# ATX12V_MAIN_VERT.net
KiCad netlist of a schematic drawn in EAGLE
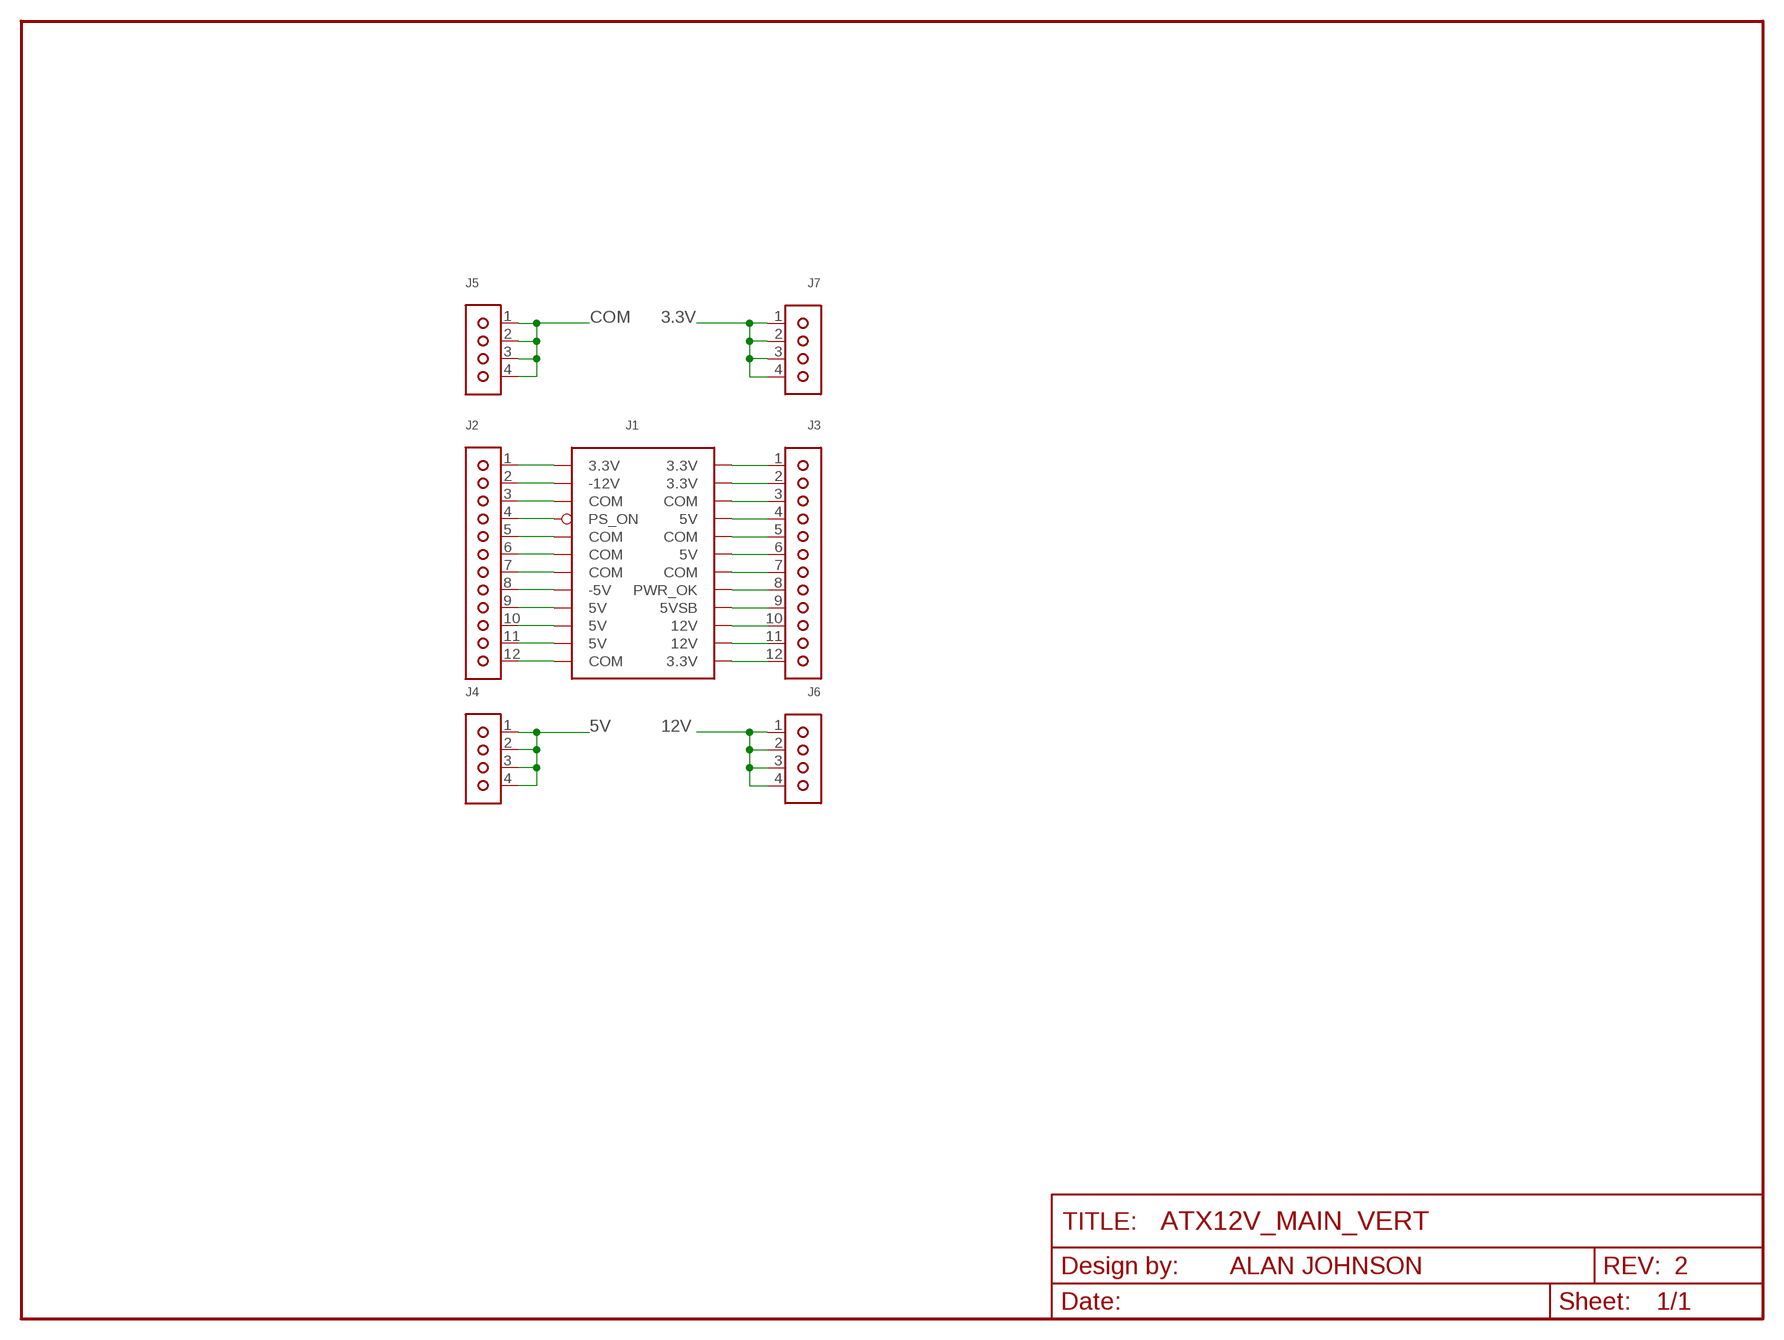
[diagram p0: schematic, sheet 1]

(export (version "E")
  (design (tool "Eeschema 10.0.6"))
  (components
    (comp (ref "J1")
      (value "ATX12V_MAIN_VERT")
      (footprint "eagle-import:44206-0007")
      (libsource (lib "eagle-import") (part "ATX12V_MAIN_VERT"))
    )
    (comp (ref "J2")
      (value "1X12")
      (footprint "eagle-import:1X12")
      (libsource (lib "eagle-import") (part "1X12"))
    )
    (comp (ref "J3")
      (value "1X12")
      (footprint "eagle-import:1X12")
      (libsource (lib "eagle-import") (part "1X12"))
    )
    (comp (ref "J4")
      (value "1X04")
      (footprint "eagle-import:1X04")
      (libsource (lib "eagle-import") (part "1X04"))
    )
    (comp (ref "J5")
      (value "1X04")
      (footprint "eagle-import:1X04")
      (libsource (lib "eagle-import") (part "1X04"))
    )
    (comp (ref "J6")
      (value "1X04")
      (footprint "eagle-import:1X04")
      (libsource (lib "eagle-import") (part "1X04"))
    )
    (comp (ref "J7")
      (value "1X04")
      (footprint "eagle-import:1X04")
      (libsource (lib "eagle-import") (part "1X04"))
    )
  )
  (nets
    (net (code "1") (name "/3.3V") (class "Default")
      (node (ref "J1") (pin "1") (pinfunction "3.3V_1") (pintype "power_in"))
      (node (ref "J1") (pin "12") (pinfunction "3.3V_12") (pintype "power_in"))
      (node (ref "J1") (pin "13") (pinfunction "3.3V_13") (pintype "power_in"))
      (node (ref "J1") (pin "2") (pinfunction "3.3V_2") (pintype "power_in"))
      (node (ref "J2") (pin "1") (pinfunction "1_1") (pintype "passive"))
      (node (ref "J3") (pin "1") (pinfunction "1_1") (pintype "passive"))
      (node (ref "J3") (pin "12") (pinfunction "12_12") (pintype "passive"))
      (node (ref "J3") (pin "2") (pinfunction "2_2") (pintype "passive"))
      (node (ref "J7") (pin "1") (pinfunction "1_1") (pintype "passive"))
      (node (ref "J7") (pin "2") (pinfunction "2_2") (pintype "passive"))
      (node (ref "J7") (pin "3") (pinfunction "3_3") (pintype "passive"))
      (node (ref "J7") (pin "4") (pinfunction "4_4") (pintype "passive"))
    )
    (net (code "2") (name "/5V") (class "Default")
      (node (ref "J1") (pin "21") (pinfunction "5V_21") (pintype "power_in"))
      (node (ref "J1") (pin "22") (pinfunction "5V_22") (pintype "power_in"))
      (node (ref "J1") (pin "23") (pinfunction "5V_23") (pintype "power_in"))
      (node (ref "J1") (pin "4") (pinfunction "5V_4") (pintype "power_in"))
      (node (ref "J1") (pin "6") (pinfunction "5V_6") (pintype "power_in"))
      (node (ref "J2") (pin "10") (pinfunction "10_10") (pintype "passive"))
      (node (ref "J2") (pin "11") (pinfunction "11_11") (pintype "passive"))
      (node (ref "J2") (pin "9") (pinfunction "9_9") (pintype "passive"))
      (node (ref "J3") (pin "4") (pinfunction "4_4") (pintype "passive"))
      (node (ref "J3") (pin "6") (pinfunction "6_6") (pintype "passive"))
      (node (ref "J4") (pin "1") (pinfunction "1_1") (pintype "passive"))
      (node (ref "J4") (pin "2") (pinfunction "2_2") (pintype "passive"))
      (node (ref "J4") (pin "3") (pinfunction "3_3") (pintype "passive"))
      (node (ref "J4") (pin "4") (pinfunction "4_4") (pintype "passive"))
    )
    (net (code "3") (name "/12V") (class "Default")
      (node (ref "J1") (pin "10") (pinfunction "12V_10") (pintype "power_in"))
      (node (ref "J1") (pin "11") (pinfunction "12V_11") (pintype "power_in"))
      (node (ref "J3") (pin "10") (pinfunction "10_10") (pintype "passive"))
      (node (ref "J3") (pin "11") (pinfunction "11_11") (pintype "passive"))
      (node (ref "J6") (pin "1") (pinfunction "1_1") (pintype "passive"))
      (node (ref "J6") (pin "2") (pinfunction "2_2") (pintype "passive"))
      (node (ref "J6") (pin "3") (pinfunction "3_3") (pintype "passive"))
      (node (ref "J6") (pin "4") (pinfunction "4_4") (pintype "passive"))
    )
    (net (code "4") (name "/COM") (class "Default")
      (node (ref "J1") (pin "15") (pinfunction "COM_15") (pintype "power_in"))
      (node (ref "J1") (pin "17") (pinfunction "COM_17") (pintype "power_in"))
      (node (ref "J1") (pin "18") (pinfunction "COM_18") (pintype "power_in"))
      (node (ref "J1") (pin "19") (pinfunction "COM_19") (pintype "power_in"))
      (node (ref "J1") (pin "24") (pinfunction "COM_24") (pintype "power_in"))
      (node (ref "J1") (pin "3") (pinfunction "COM_3") (pintype "power_in"))
      (node (ref "J1") (pin "5") (pinfunction "COM_5") (pintype "power_in"))
      (node (ref "J1") (pin "7") (pinfunction "COM_7") (pintype "power_in"))
      (node (ref "J2") (pin "12") (pinfunction "12_12") (pintype "passive"))
      (node (ref "J2") (pin "3") (pinfunction "3_3") (pintype "passive"))
      (node (ref "J2") (pin "5") (pinfunction "5_5") (pintype "passive"))
      (node (ref "J2") (pin "6") (pinfunction "6_6") (pintype "passive"))
      (node (ref "J2") (pin "7") (pinfunction "7_7") (pintype "passive"))
      (node (ref "J3") (pin "3") (pinfunction "3_3") (pintype "passive"))
      (node (ref "J3") (pin "5") (pinfunction "5_5") (pintype "passive"))
      (node (ref "J3") (pin "7") (pinfunction "7_7") (pintype "passive"))
      (node (ref "J5") (pin "1") (pinfunction "1_1") (pintype "passive"))
      (node (ref "J5") (pin "2") (pinfunction "2_2") (pintype "passive"))
      (node (ref "J5") (pin "3") (pinfunction "3_3") (pintype "passive"))
      (node (ref "J5") (pin "4") (pinfunction "4_4") (pintype "passive"))
    )
    (net (code "5") (name "Net-(J1--5V)") (class "Default")
      (node (ref "J1") (pin "20") (pinfunction "-5V_20") (pintype "power_in"))
      (node (ref "J2") (pin "8") (pinfunction "8_8") (pintype "passive"))
    )
    (net (code "6") (name "Net-(J1--12V)") (class "Default")
      (node (ref "J1") (pin "14") (pinfunction "-12V_14") (pintype "power_in"))
      (node (ref "J2") (pin "2") (pinfunction "2_2") (pintype "passive"))
    )
    (net (code "7") (name "Net-(J1-5VSB)") (class "Default")
      (node (ref "J1") (pin "9") (pinfunction "5VSB_9") (pintype "power_in"))
      (node (ref "J3") (pin "9") (pinfunction "9_9") (pintype "passive"))
    )
    (net (code "8") (name "Net-(J1-PS_ON)") (class "Default")
      (node (ref "J1") (pin "16") (pinfunction "PS_ON_16") (pintype "power_in"))
      (node (ref "J2") (pin "4") (pinfunction "4_4") (pintype "passive"))
    )
    (net (code "9") (name "Net-(J1-PWR_OK)") (class "Default")
      (node (ref "J1") (pin "8") (pinfunction "PWR_OK_8") (pintype "power_in"))
      (node (ref "J3") (pin "8") (pinfunction "8_8") (pintype "passive"))
    )
  )
)
